# Preamp_protection.net
KiCad netlist of a schematic drawn in Altium Designer
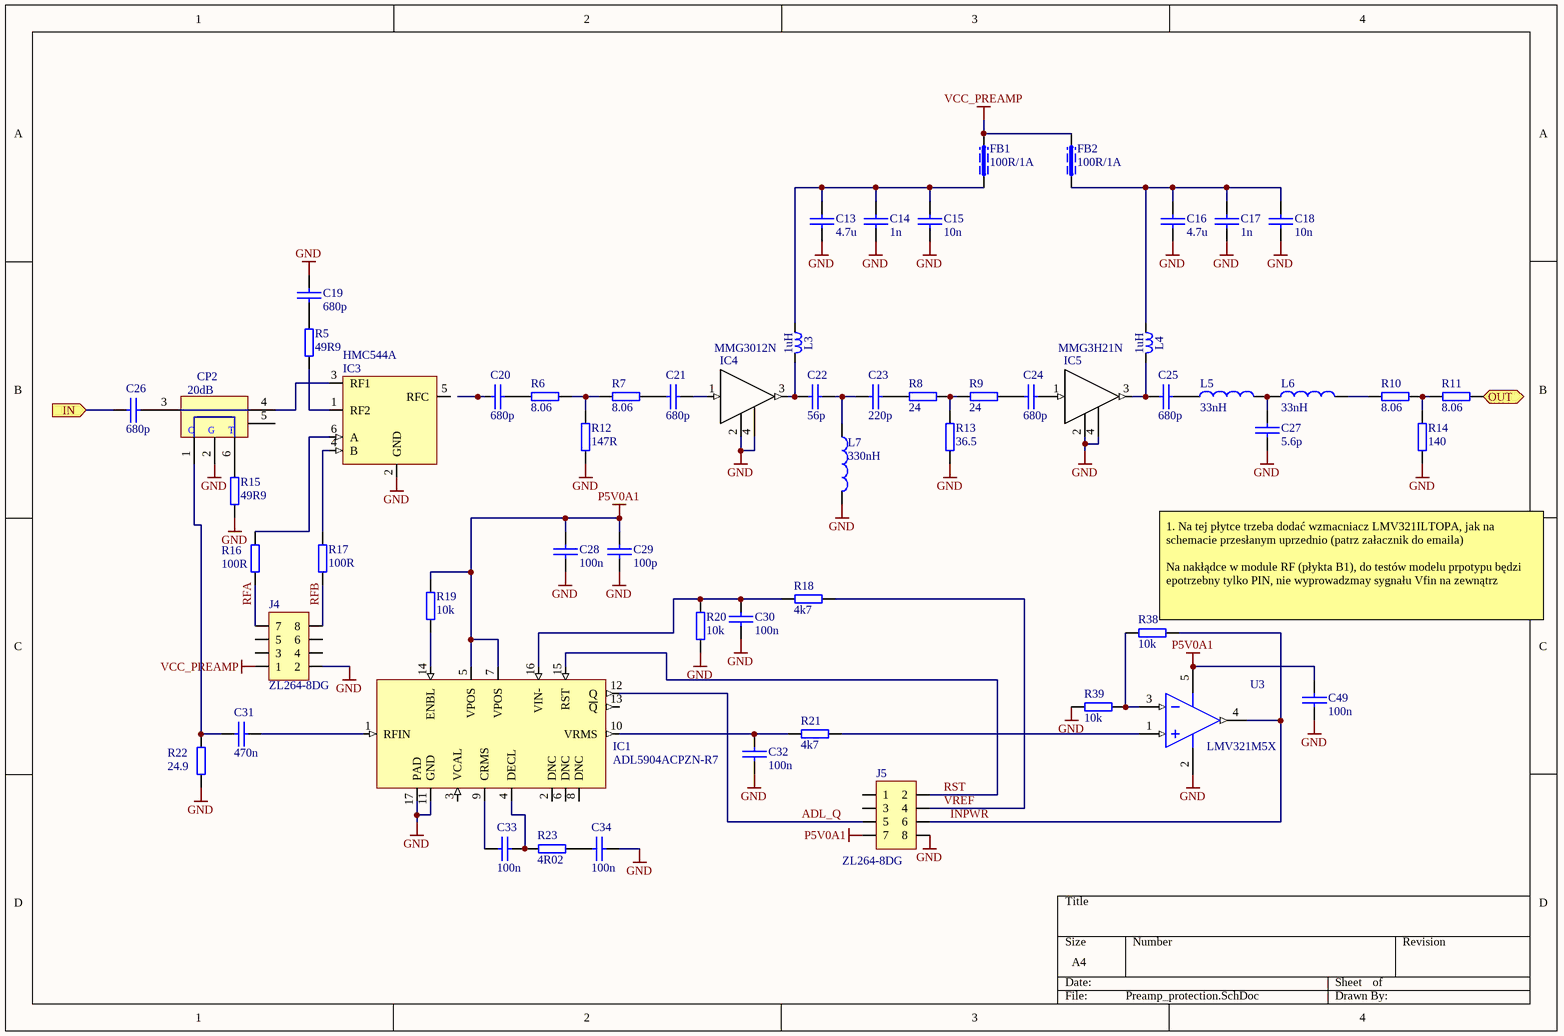
[diagram p0: Preamp_protection.SchDoc]

(export (version "E")
  (design (tool "Eeschema 10.0.6"))
  (components
    (comp (ref "C13")
      (value "4.7u")
      (footprint "0603C")
      (description "Capacitor SMD")
      (fields (field (name "PART") "GRM21BR71C475KE51L"))
      (libsource (lib "LIBRARY_SCH") (part "CAP_SMD_0603"))
    )
    (comp (ref "C14")
      (value "1n")
      (footprint "0603C")
      (description "Capacitor SMD")
      (fields (field (name "PART") "GRM1885C1H102JA01D"))
      (libsource (lib "LIBRARY_SCH") (part "CAP_SMD_0603"))
    )
    (comp (ref "C15")
      (value "10n")
      (footprint "0603C")
      (description "Capacitor SMD")
      (fields (field (name "PART") "GRM1885C1H103JA01D"))
      (libsource (lib "LIBRARY_SCH") (part "CAP_SMD_0603"))
    )
    (comp (ref "C16")
      (value "4.7u")
      (footprint "0603C")
      (description "Capacitor SMD")
      (fields (field (name "PART") "GRM21BR71C475KE51L"))
      (libsource (lib "LIBRARY_SCH") (part "CAP_SMD_0603"))
    )
    (comp (ref "C17")
      (value "1n")
      (footprint "0603C")
      (description "Capacitor SMD")
      (fields (field (name "PART") "GRM1885C1H102JA01D"))
      (libsource (lib "LIBRARY_SCH") (part "CAP_SMD_0603"))
    )
    (comp (ref "C18")
      (value "10n")
      (footprint "0603C")
      (description "Capacitor SMD")
      (fields (field (name "PART") "GRM1885C1H103JA01D"))
      (libsource (lib "LIBRARY_SCH") (part "CAP_SMD_0603"))
    )
    (comp (ref "C19")
      (value "680p")
      (footprint "0603C")
      (description "Capacitor SMD")
      (fields (field (name "PART") "GRM1555C1H681GA01"))
      (libsource (lib "LIBRARY_SCH") (part "CAP_SMD_0603"))
    )
    (comp (ref "C20")
      (value "680p")
      (footprint "0603C")
      (description "Capacitor SMD")
      (fields (field (name "PART") "GRM1555C1H681GA01"))
      (libsource (lib "LIBRARY_SCH") (part "CAP_SMD_0603"))
    )
    (comp (ref "C21")
      (value "680p")
      (footprint "0603C")
      (description "Capacitor SMD")
      (fields (field (name "PART") "GRM1555C1H681GA01"))
      (libsource (lib "LIBRARY_SCH") (part "CAP_SMD_0603"))
    )
    (comp (ref "C22")
      (value "56p")
      (footprint "0603C")
      (description "Capacitor SMD")
      (fields (field (name "PART") "GRM1885C1H560GA01J"))
      (libsource (lib "LIBRARY_SCH") (part "CAP_SMD_0603"))
    )
    (comp (ref "C23")
      (value "220p")
      (footprint "0603C")
      (description "Capacitor SMD")
      (fields (field (name "PART") "GRM1885C1H221GA01D"))
      (libsource (lib "LIBRARY_SCH") (part "CAP_SMD_0603"))
    )
    (comp (ref "C24")
      (value "680p")
      (footprint "0603C")
      (description "Capacitor SMD")
      (fields (field (name "PART") "GRM1555C1H681GA01"))
      (libsource (lib "LIBRARY_SCH") (part "CAP_SMD_0603"))
    )
    (comp (ref "C25")
      (value "680p")
      (footprint "0603C")
      (description "Capacitor SMD")
      (fields (field (name "PART") "GRM1555C1H681GA01"))
      (libsource (lib "LIBRARY_SCH") (part "CAP_SMD_0603"))
    )
    (comp (ref "C26")
      (value "680p")
      (footprint "0603C")
      (description "Capacitor SMD")
      (fields (field (name "PART") "GRM1555C1H681GA01"))
      (libsource (lib "LIBRARY_SCH") (part "CAP_SMD_0603"))
    )
    (comp (ref "C27")
      (value "5.6p")
      (footprint "0603C")
      (description "Capacitor SMD")
      (fields (field (name "PART") "GQM1885C2A5R6BB01D"))
      (libsource (lib "LIBRARY_SCH") (part "CAP_SMD_0603"))
    )
    (comp (ref "C28")
      (value "100n")
      (footprint "0603C")
      (description "Capacitor SMD")
      (fields (field (name "PART") "GRM188L81H104KA93D"))
      (libsource (lib "LIBRARY_SCH") (part "CAP_SMD_0603"))
    )
    (comp (ref "C29")
      (value "100p")
      (footprint "0603C")
      (description "Capacitor SMD")
      (fields (field (name "PART") "C1608NP01H101J080AA"))
      (libsource (lib "LIBRARY_SCH") (part "CAP_SMD_0603"))
    )
    (comp (ref "C30")
      (value "100n")
      (footprint "0603C")
      (description "Capacitor SMD")
      (fields (field (name "PART") "GRM188L81H104KA93D"))
      (libsource (lib "LIBRARY_SCH") (part "CAP_SMD_0603"))
    )
    (comp (ref "C31")
      (value "470n")
      (footprint "0603C")
      (description "Capacitor SMD")
      (fields (field (name "PART") "GRM188R71A474KA61D"))
      (libsource (lib "LIBRARY_SCH") (part "CAP_SMD_0603"))
    )
    (comp (ref "C32")
      (value "100n")
      (footprint "0603C")
      (description "Capacitor SMD")
      (fields (field (name "PART") "GRM188L81H104KA93D"))
      (libsource (lib "LIBRARY_SCH") (part "CAP_SMD_0603"))
    )
    (comp (ref "C33")
      (value "100n")
      (footprint "0603C")
      (description "Capacitor SMD")
      (fields (field (name "PART") "GRM188L81H104KA93D"))
      (libsource (lib "LIBRARY_SCH") (part "CAP_SMD_0603"))
    )
    (comp (ref "C34")
      (value "100n")
      (footprint "0603C")
      (description "Capacitor SMD")
      (fields (field (name "PART") "GRM188L81H104KA93D"))
      (libsource (lib "LIBRARY_SCH") (part "CAP_SMD_0603"))
    )
    (comp (ref "C49")
      (value "100n")
      (footprint "0603C")
      (description "Capacitor SMD")
      (fields (field (name "PART") "GRM188L81H104KA93D"))
      (libsource (lib "LIBRARY_SCH") (part "CAP_SMD_0603"))
    )
    (comp (ref "CP2")
      (value "20dB")
      (footprint "XFMR_MINI-CIRCUITS_AT224")
      (description "50 Ohms directional coupler")
      (fields
        (field (name "PART NUMBER") "XFMR_MINI-CIRCUITS_TCD-20-4X+")
        (field (name "MANUFACTURER") "MINI-CIRCUITS")
        (field (name "AUTHOR") "GK")
      )
      (libsource (lib "LIBRARY_SCH") (part "RF_Coupler_TCD-20-4X"))
    )
    (comp (ref "FB1")
      (value "100R/1A")
      (footprint "0603L")
      (description "ferrite bead 100R@100MHz 1A")
      (libsource (lib "LIBRARY_SCH") (part "L_FERRITE_BEAD_0603"))
    )
    (comp (ref "FB2")
      (value "100R/1A")
      (footprint "0603L")
      (description "ferrite bead 100R@100MHz 1A")
      (libsource (lib "LIBRARY_SCH") (part "L_FERRITE_BEAD_0603"))
    )
    (comp (ref "IC1")
      (value "ADL5904ACPZN-R7")
      (footprint "QFN50P300X300X80_HS-17N")
      (description "DC   to 6 GHz  , 45 dB DC  to 6 GHz , 45 dB TruPwr Detector with Envelope Threshold Detection")
      (libsource (lib "LIBRARY_SCH") (part "ADL5904"))
    )
    (comp (ref "IC3")
      (value "HMC544A")
      (footprint "SOT95P280X130-6N")
      (libsource (lib "LIBRARY_SCH") (part "RF_HMC544AE"))
    )
    (comp (ref "IC4")
      (value "MMG3012N")
      (footprint "SOT89-150P410X170-3N")
      (description "Broadband High Linearity Amplifier")
      (libsource (lib "LIBRARY_SCH") (part "RF_MMG3012N"))
    )
    (comp (ref "IC5")
      (value "MMG3H21N")
      (footprint "SOT89-150P410X170-3N")
      (description "Broadband High Linearity Amplifier")
      (libsource (lib "LIBRARY_SCH") (part "RF_MMG3H21N"))
    )
    (comp (ref "J4")
      (value "ZL264-8DG")
      (footprint "ZL264-8DG")
      (description "2.54mm pitch connector")
      (libsource (lib "") (part "CON_2X4 2.54 SMT FEM_1"))
    )
    (comp (ref "J5")
      (value "ZL264-8DG")
      (footprint "ZL264-8DG")
      (description "2.54mm pitch connector")
      (libsource (lib "LIBRARY_SCH") (part "CON_2X4 2.54 SMT FEM"))
    )
    (comp (ref "L3")
      (value "1uH")
      (footprint "INDP2520X18L")
      (description "100uH, 60mA, 21R")
      (fields (field (name "PART") "LQW2UAS1R0J00L") (field (name "AUTHOR") "GK"))
      (libsource (lib "LIBRARY_SCH") (part "L_1008_100u"))
    )
    (comp (ref "L4")
      (value "1uH")
      (footprint "INDP2520X18L")
      (description "100uH, 60mA, 21R")
      (fields (field (name "PART") "LQW2UAS1R0J00L") (field (name "AUTHOR") "GK"))
      (libsource (lib "LIBRARY_SCH") (part "L_1008_100u"))
    )
    (comp (ref "L5")
      (value "33nH")
      (footprint "0603L")
      (description "1uH, 25mA, 0.6R")
      (fields (field (name "PART") "LQW18AS33NG00D"))
      (libsource (lib "") (part "L_0603_1uH_1"))
    )
    (comp (ref "L6")
      (value "33nH")
      (footprint "0603L")
      (description "1uH, 25mA, 0.6R")
      (fields (field (name "PART") "LQW18AS33NG00D"))
      (libsource (lib "") (part "L_0603_1uH_1"))
    )
    (comp (ref "L7")
      (value "330nH")
      (footprint "0603L")
      (description "1uH, 25mA, 0.6R")
      (fields (field (name "PART") "LQW18ANR33G00D"))
      (libsource (lib "LIBRARY_SCH") (part "L_0603_1uH"))
    )
    (comp (ref "R5")
      (value "49R9")
      (footprint "0603R")
      (description "SMD Resistor")
      (fields (field (name "PART") "MCT0603PD4999DP500"))
      (libsource (lib "LIBRARY_SCH") (part "RES_0603"))
    )
    (comp (ref "R6")
      (value "8.06")
      (footprint "0603R")
      (description "SMD Resistor")
      (fields (field (name "PART") "CPF0805B8R06E1"))
      (libsource (lib "LIBRARY_SCH") (part "RES_0603"))
    )
    (comp (ref "R7")
      (value "8.06")
      (footprint "0603R")
      (description "SMD Resistor")
      (fields (field (name "PART") "CPF0805B8R06E1"))
      (libsource (lib "LIBRARY_SCH") (part "RES_0603"))
    )
    (comp (ref "R8")
      (value "24")
      (footprint "0603R")
      (description "SMD Resistor")
      (fields (field (name "PART") "CPF0805B24RE1"))
      (libsource (lib "LIBRARY_SCH") (part "RES_0603"))
    )
    (comp (ref "R9")
      (value "24")
      (footprint "0603R")
      (description "SMD Resistor")
      (fields (field (name "PART") "CPF0805B24RE1"))
      (libsource (lib "LIBRARY_SCH") (part "RES_0603"))
    )
    (comp (ref "R10")
      (value "8.06")
      (footprint "0603R")
      (description "SMD Resistor")
      (fields (field (name "PART") "CPF0805B8R06E1"))
      (libsource (lib "LIBRARY_SCH") (part "RES_0603"))
    )
    (comp (ref "R11")
      (value "8.06")
      (footprint "0603R")
      (description "SMD Resistor")
      (fields (field (name "PART") "CPF0805B8R06E1"))
      (libsource (lib "LIBRARY_SCH") (part "RES_0603"))
    )
    (comp (ref "R12")
      (value "147R")
      (footprint "0603R")
      (description "SMD Resistor")
      (fields (field (name "PART") "CPF0805B147RE1"))
      (libsource (lib "LIBRARY_SCH") (part "RES_0603"))
    )
    (comp (ref "R13")
      (value "36.5")
      (footprint "0603R")
      (description "SMD Resistor")
      (fields (field (name "PART") "CPF0805B36R5E1"))
      (libsource (lib "LIBRARY_SCH") (part "RES_0603"))
    )
    (comp (ref "R14")
      (value "140")
      (footprint "0603R")
      (description "SMD Resistor")
      (libsource (lib "LIBRARY_SCH") (part "RES_0603"))
    )
    (comp (ref "R15")
      (value "49R9")
      (footprint "0603R")
      (description "SMD Resistor")
      (fields (field (name "PART") "MCT0603PD4999DP500"))
      (libsource (lib "LIBRARY_SCH") (part "RES_0603"))
    )
    (comp (ref "R16")
      (value "100R")
      (footprint "0603R")
      (description "SMD Resistor")
      (fields (field (name "PART") "CRCW0603100RJNEA"))
      (libsource (lib "LIBRARY_SCH") (part "RES_0603"))
    )
    (comp (ref "R17")
      (value "100R")
      (footprint "0603R")
      (description "SMD Resistor")
      (fields (field (name "PART") "CRCW0603100RJNEA"))
      (libsource (lib "LIBRARY_SCH") (part "RES_0603"))
    )
    (comp (ref "R18")
      (value "4k7")
      (footprint "0603R")
      (description "SMD Resistor")
      (fields (field (name "PART") "CR0603-FX-4701ELF"))
      (libsource (lib "LIBRARY_SCH") (part "RES_0603"))
    )
    (comp (ref "R19")
      (value "10k")
      (footprint "0603R")
      (description "SMD Resistor")
      (fields (field (name "PART") "CRCW060310K0FKEA"))
      (libsource (lib "LIBRARY_SCH") (part "RES_0603"))
    )
    (comp (ref "R20")
      (value "10k")
      (footprint "0603R")
      (description "SMD Resistor")
      (fields (field (name "PART") "CRCW060310K0FKEA"))
      (libsource (lib "LIBRARY_SCH") (part "RES_0603"))
    )
    (comp (ref "R21")
      (value "4k7")
      (footprint "0603R")
      (description "SMD Resistor")
      (fields (field (name "PART") "CR0603-FX-4701ELF"))
      (libsource (lib "LIBRARY_SCH") (part "RES_0603"))
    )
    (comp (ref "R22")
      (value "24.9")
      (footprint "0603R")
      (description "SMD Resistor")
      (fields (field (name "PART") "CPF0603F24R9C1"))
      (libsource (lib "LIBRARY_SCH") (part "RES_0603"))
    )
    (comp (ref "R23")
      (value "4R02")
      (footprint "0603R")
      (description "SMD Resistor")
      (fields (field (name "PART") "CRCW06034R02FKEA"))
      (libsource (lib "LIBRARY_SCH") (part "RES_0603"))
    )
    (comp (ref "R38")
      (value "10k")
      (footprint "0603R")
      (description "SMD Resistor")
      (fields (field (name "PART") "CRCW060310K0FKEA"))
      (libsource (lib "LIBRARY_SCH") (part "RES_0603"))
    )
    (comp (ref "R39")
      (value "10k")
      (footprint "0603R")
      (description "SMD Resistor")
      (fields (field (name "PART") "CRCW060310K0FKEA"))
      (libsource (lib "LIBRARY_SCH") (part "RES_0603"))
    )
    (comp (ref "U3")
      (value "LMV321M5X")
      (footprint "DBV0005A_N")
      (description "General Purpose, Low Voltage, Rail-to-Rail Output Operational Amplifiers, 5-pin SOT-23")
      (fields (field (name "MANUFACTURER") "Texas Instruments"))
      (libsource (lib "Altium Content Vault") (part "AMP-OPA-LMV551-5"))
    )
  )
  (nets
    (net (code "1") (name "/ADL_Q") (class "Default")
      (node (ref "IC1") (pin "12") (pinfunction "Q_12") (pintype "output"))
      (node (ref "J5") (pin "5") (pinfunction "5_5") (pintype "passive"))
    )
    (net (code "2") (name "/IN") (class "Default")
      (node (ref "C26") (pin "1") (pinfunction "1_1") (pintype "passive"))
    )
    (net (code "3") (name "/INPWR") (class "Default")
      (node (ref "J5") (pin "6") (pinfunction "6_6") (pintype "passive"))
      (node (ref "R38") (pin "1") (pinfunction "1_1") (pintype "passive"))
      (node (ref "U3") (pin "4") (pinfunction "OUT_4") (pintype "output"))
    )
    (net (code "4") (name "/OUT") (class "Default")
      (node (ref "R11") (pin "1") (pinfunction "1_1") (pintype "passive"))
    )
    (net (code "5") (name "/RFA") (class "Default")
      (node (ref "J4") (pin "7") (pinfunction "7_7") (pintype "passive"))
      (node (ref "R16") (pin "2") (pinfunction "2_2") (pintype "passive"))
    )
    (net (code "6") (name "/RFB") (class "Default")
      (node (ref "J4") (pin "8") (pinfunction "8_8") (pintype "passive"))
      (node (ref "R17") (pin "2") (pinfunction "2_2") (pintype "passive"))
    )
    (net (code "7") (name "/RST") (class "Default")
      (node (ref "IC1") (pin "15") (pinfunction "RST_15") (pintype "input"))
      (node (ref "J5") (pin "2") (pinfunction "2_2") (pintype "passive"))
    )
    (net (code "8") (name "/VREF") (class "Default")
      (node (ref "J5") (pin "4") (pinfunction "4_4") (pintype "passive"))
      (node (ref "R18") (pin "1") (pinfunction "1_1") (pintype "passive"))
    )
    (net (code "9") (name "GND") (class "Default")
      (node (ref "C13") (pin "2") (pinfunction "2_2") (pintype "passive"))
      (node (ref "C14") (pin "2") (pinfunction "2_2") (pintype "passive"))
      (node (ref "C15") (pin "2") (pinfunction "2_2") (pintype "passive"))
      (node (ref "C16") (pin "2") (pinfunction "2_2") (pintype "passive"))
      (node (ref "C17") (pin "2") (pinfunction "2_2") (pintype "passive"))
      (node (ref "C18") (pin "2") (pinfunction "2_2") (pintype "passive"))
      (node (ref "C19") (pin "2") (pinfunction "2_2") (pintype "passive"))
      (node (ref "C27") (pin "1") (pinfunction "1_1") (pintype "passive"))
      (node (ref "C28") (pin "2") (pinfunction "2_2") (pintype "passive"))
      (node (ref "C29") (pin "2") (pinfunction "2_2") (pintype "passive"))
      (node (ref "C30") (pin "1") (pinfunction "1_1") (pintype "passive"))
      (node (ref "C32") (pin "1") (pinfunction "1_1") (pintype "passive"))
      (node (ref "C34") (pin "2") (pinfunction "2_2") (pintype "passive"))
      (node (ref "C49") (pin "1") (pinfunction "1_1") (pintype "passive"))
      (node (ref "CP2") (pin "2") (pinfunction "NC_2") (pintype "passive"))
      (node (ref "IC1") (pin "11") (pinfunction "GND_11") (pintype "power_in"))
      (node (ref "IC1") (pin "17") (pinfunction "PAD_17") (pintype "power_in"))
      (node (ref "IC3") (pin "2") (pinfunction "GND_2") (pintype "power_in"))
      (node (ref "IC4") (pin "2") (pinfunction "G_2") (pintype "power_in"))
      (node (ref "IC4") (pin "4") (pinfunction "G_4") (pintype "power_in"))
      (node (ref "IC5") (pin "2") (pinfunction "G_2") (pintype "power_in"))
      (node (ref "IC5") (pin "4") (pinfunction "G_4") (pintype "power_in"))
      (node (ref "J4") (pin "2") (pinfunction "2_2") (pintype "passive"))
      (node (ref "J5") (pin "8") (pinfunction "8_8") (pintype "passive"))
      (node (ref "L7") (pin "2") (pinfunction "2_2") (pintype "passive"))
      (node (ref "R12") (pin "1") (pinfunction "1_1") (pintype "passive"))
      (node (ref "R13") (pin "2") (pinfunction "2_2") (pintype "passive"))
      (node (ref "R14") (pin "2") (pinfunction "2_2") (pintype "passive"))
      (node (ref "R15") (pin "2") (pinfunction "2_2") (pintype "passive"))
      (node (ref "R20") (pin "1") (pinfunction "1_1") (pintype "passive"))
      (node (ref "R22") (pin "2") (pinfunction "2_2") (pintype "passive"))
      (node (ref "R39") (pin "2") (pinfunction "2_2") (pintype "passive"))
      (node (ref "U3") (pin "2") (pinfunction "V-_2") (pintype "power_in"))
    )
    (net (code "10") (name "Net-(C13-Pad1)") (class "Default")
      (node (ref "C13") (pin "1") (pinfunction "1_1") (pintype "passive"))
      (node (ref "C14") (pin "1") (pinfunction "1_1") (pintype "passive"))
      (node (ref "C15") (pin "1") (pinfunction "1_1") (pintype "passive"))
      (node (ref "FB1") (pin "1") (pinfunction "1_1") (pintype "passive"))
      (node (ref "L3") (pin "1") (pinfunction "1_1") (pintype "passive"))
    )
    (net (code "11") (name "Net-(C16-Pad1)") (class "Default")
      (node (ref "C16") (pin "1") (pinfunction "1_1") (pintype "passive"))
      (node (ref "C17") (pin "1") (pinfunction "1_1") (pintype "passive"))
      (node (ref "C18") (pin "1") (pinfunction "1_1") (pintype "passive"))
      (node (ref "FB2") (pin "1") (pinfunction "1_1") (pintype "passive"))
      (node (ref "L4") (pin "1") (pinfunction "1_1") (pintype "passive"))
    )
    (net (code "12") (name "Net-(C19-Pad1)") (class "Default")
      (node (ref "C19") (pin "1") (pinfunction "1_1") (pintype "passive"))
      (node (ref "R5") (pin "1") (pinfunction "1_1") (pintype "passive"))
    )
    (net (code "13") (name "Net-(C20-Pad2)") (class "Default")
      (node (ref "C20") (pin "2") (pinfunction "2_2") (pintype "passive"))
      (node (ref "R6") (pin "2") (pinfunction "2_2") (pintype "passive"))
    )
    (net (code "14") (name "Net-(C21-Pad1)") (class "Default")
      (node (ref "C21") (pin "1") (pinfunction "1_1") (pintype "passive"))
      (node (ref "R7") (pin "1") (pinfunction "1_1") (pintype "passive"))
    )
    (net (code "15") (name "Net-(C22-Pad2)") (class "Default")
      (node (ref "C22") (pin "2") (pinfunction "2_2") (pintype "passive"))
      (node (ref "C23") (pin "1") (pinfunction "1_1") (pintype "passive"))
      (node (ref "L7") (pin "1") (pinfunction "1_1") (pintype "passive"))
    )
    (net (code "16") (name "Net-(C23-Pad2)") (class "Default")
      (node (ref "C23") (pin "2") (pinfunction "2_2") (pintype "passive"))
      (node (ref "R8") (pin "2") (pinfunction "2_2") (pintype "passive"))
    )
    (net (code "17") (name "Net-(C24-Pad1)") (class "Default")
      (node (ref "C24") (pin "1") (pinfunction "1_1") (pintype "passive"))
      (node (ref "R9") (pin "1") (pinfunction "1_1") (pintype "passive"))
    )
    (net (code "18") (name "Net-(C25-Pad2)") (class "Default")
      (node (ref "C25") (pin "2") (pinfunction "2_2") (pintype "passive"))
      (node (ref "L5") (pin "1") (pinfunction "1_1") (pintype "passive"))
    )
    (net (code "19") (name "Net-(C27-Pad2)") (class "Default")
      (node (ref "C27") (pin "2") (pinfunction "2_2") (pintype "passive"))
      (node (ref "L5") (pin "2") (pinfunction "2_2") (pintype "passive"))
      (node (ref "L6") (pin "1") (pinfunction "1_1") (pintype "passive"))
    )
    (net (code "20") (name "Net-(C34-Pad1)") (class "Default")
      (node (ref "C34") (pin "1") (pinfunction "1_1") (pintype "passive"))
      (node (ref "R23") (pin "2") (pinfunction "2_2") (pintype "passive"))
    )
    (net (code "21") (name "Net-(CP2-PDOT)") (class "Default")
      (node (ref "CP2") (pin "6") (pinfunction "PDOT_6") (pintype "passive"))
      (node (ref "R15") (pin "1") (pinfunction "1_1") (pintype "passive"))
    )
    (net (code "22") (name "Net-(CP2-S)") (class "Default")
      (node (ref "C26") (pin "2") (pinfunction "2_2") (pintype "passive"))
      (node (ref "CP2") (pin "3") (pinfunction "S_3") (pintype "passive"))
    )
    (net (code "23") (name "Net-(CP2-SDOT)") (class "Default")
      (node (ref "C31") (pin "1") (pinfunction "1_1") (pintype "passive"))
      (node (ref "CP2") (pin "1") (pinfunction "SDOT_1") (pintype "passive"))
      (node (ref "R22") (pin "1") (pinfunction "1_1") (pintype "passive"))
    )
    (net (code "24") (name "Net-(IC1-CRMS)") (class "Default")
      (node (ref "C33") (pin "1") (pinfunction "1_1") (pintype "passive"))
      (node (ref "IC1") (pin "9") (pinfunction "CRMS_9") (pintype "passive"))
    )
    (net (code "25") (name "Net-(IC1-DECL)") (class "Default")
      (node (ref "C33") (pin "2") (pinfunction "2_2") (pintype "passive"))
      (node (ref "IC1") (pin "4") (pinfunction "DECL_4") (pintype "passive"))
      (node (ref "R23") (pin "1") (pinfunction "1_1") (pintype "passive"))
    )
    (net (code "26") (name "Net-(IC1-ENBL)") (class "Default")
      (node (ref "IC1") (pin "14") (pinfunction "ENBL_14") (pintype "input"))
      (node (ref "R19") (pin "2") (pinfunction "2_2") (pintype "passive"))
    )
    (net (code "27") (name "Net-(IC1-RFIN)") (class "Default")
      (node (ref "C31") (pin "2") (pinfunction "2_2") (pintype "passive"))
      (node (ref "IC1") (pin "1") (pinfunction "RFIN_1") (pintype "input"))
    )
    (net (code "28") (name "Net-(IC1-VIN-)") (class "Default")
      (node (ref "C30") (pin "2") (pinfunction "2_2") (pintype "passive"))
      (node (ref "IC1") (pin "16") (pinfunction "VIN-_16") (pintype "input"))
      (node (ref "R18") (pin "2") (pinfunction "2_2") (pintype "passive"))
      (node (ref "R20") (pin "2") (pinfunction "2_2") (pintype "passive"))
    )
    (net (code "29") (name "Net-(IC1-VRMS)") (class "Default")
      (node (ref "C32") (pin "2") (pinfunction "2_2") (pintype "passive"))
      (node (ref "IC1") (pin "10") (pinfunction "VRMS_10") (pintype "output"))
      (node (ref "R21") (pin "2") (pinfunction "2_2") (pintype "passive"))
    )
    (net (code "30") (name "Net-(IC3-A)") (class "Default")
      (node (ref "IC3") (pin "6") (pinfunction "A_6") (pintype "input"))
      (node (ref "R16") (pin "1") (pinfunction "1_1") (pintype "passive"))
    )
    (net (code "31") (name "Net-(IC3-B)") (class "Default")
      (node (ref "IC3") (pin "4") (pinfunction "B_4") (pintype "input"))
      (node (ref "R17") (pin "1") (pinfunction "1_1") (pintype "passive"))
    )
    (net (code "32") (name "Net-(IC3-RF1)") (class "Default")
      (node (ref "CP2") (pin "4") (pinfunction "P_4") (pintype "passive"))
      (node (ref "IC3") (pin "3") (pinfunction "RF1_3") (pintype "bidirectional"))
    )
    (net (code "33") (name "Net-(IC3-RF2)") (class "Default")
      (node (ref "IC3") (pin "1") (pinfunction "RF2_1") (pintype "bidirectional"))
      (node (ref "R5") (pin "2") (pinfunction "2_2") (pintype "passive"))
    )
    (net (code "34") (name "Net-(IC4-IN)") (class "Default")
      (node (ref "C21") (pin "2") (pinfunction "2_2") (pintype "passive"))
      (node (ref "IC4") (pin "1") (pinfunction "IN_1") (pintype "input"))
    )
    (net (code "35") (name "Net-(IC4-OUT)") (class "Default")
      (node (ref "C22") (pin "1") (pinfunction "1_1") (pintype "passive"))
      (node (ref "IC4") (pin "3") (pinfunction "OUT_3") (pintype "output"))
      (node (ref "L3") (pin "2") (pinfunction "2_2") (pintype "passive"))
    )
    (net (code "36") (name "Net-(IC5-IN)") (class "Default")
      (node (ref "C24") (pin "2") (pinfunction "2_2") (pintype "passive"))
      (node (ref "IC5") (pin "1") (pinfunction "IN_1") (pintype "input"))
    )
    (net (code "37") (name "Net-(IC5-OUT)") (class "Default")
      (node (ref "C25") (pin "1") (pinfunction "1_1") (pintype "passive"))
      (node (ref "IC5") (pin "3") (pinfunction "OUT_3") (pintype "output"))
      (node (ref "L4") (pin "2") (pinfunction "2_2") (pintype "passive"))
    )
    (net (code "38") (name "Net-(L6-Pad2)") (class "Default")
      (node (ref "L6") (pin "2") (pinfunction "2_2") (pintype "passive"))
      (node (ref "R10") (pin "2") (pinfunction "2_2") (pintype "passive"))
    )
    (net (code "39") (name "Net-(R10-Pad1)") (class "Default")
      (node (ref "R10") (pin "1") (pinfunction "1_1") (pintype "passive"))
      (node (ref "R11") (pin "2") (pinfunction "2_2") (pintype "passive"))
      (node (ref "R14") (pin "1") (pinfunction "1_1") (pintype "passive"))
    )
    (net (code "40") (name "Net-(R12-Pad2)") (class "Default")
      (node (ref "R12") (pin "2") (pinfunction "2_2") (pintype "passive"))
      (node (ref "R6") (pin "1") (pinfunction "1_1") (pintype "passive"))
      (node (ref "R7") (pin "2") (pinfunction "2_2") (pintype "passive"))
    )
    (net (code "41") (name "Net-(R13-Pad1)") (class "Default")
      (node (ref "R13") (pin "1") (pinfunction "1_1") (pintype "passive"))
      (node (ref "R8") (pin "1") (pinfunction "1_1") (pintype "passive"))
      (node (ref "R9") (pin "2") (pinfunction "2_2") (pintype "passive"))
    )
    (net (code "42") (name "Net-(U3-IN+)") (class "Default")
      (node (ref "R21") (pin "1") (pinfunction "1_1") (pintype "passive"))
      (node (ref "U3") (pin "1") (pinfunction "IN+_1") (pintype "input"))
    )
    (net (code "43") (name "Net-(U3-IN-)") (class "Default")
      (node (ref "R38") (pin "2") (pinfunction "2_2") (pintype "passive"))
      (node (ref "R39") (pin "1") (pinfunction "1_1") (pintype "passive"))
      (node (ref "U3") (pin "3") (pinfunction "IN-_3") (pintype "input"))
    )
    (net (code "44") (name "P5V0A1") (class "Default")
      (node (ref "C28") (pin "1") (pinfunction "1_1") (pintype "passive"))
      (node (ref "C29") (pin "1") (pinfunction "1_1") (pintype "passive"))
      (node (ref "C49") (pin "2") (pinfunction "2_2") (pintype "passive"))
      (node (ref "IC1") (pin "5") (pinfunction "VPOS_5") (pintype "power_in"))
      (node (ref "IC1") (pin "7") (pinfunction "VPOS_7") (pintype "power_in"))
      (node (ref "J5") (pin "7") (pinfunction "7_7") (pintype "passive"))
      (node (ref "R19") (pin "1") (pinfunction "1_1") (pintype "passive"))
      (node (ref "U3") (pin "5") (pinfunction "V+_5") (pintype "power_in"))
    )
    (net (code "45") (name "VCC_PREAMP") (class "Default")
      (node (ref "FB1") (pin "2") (pinfunction "2_2") (pintype "passive"))
      (node (ref "FB2") (pin "2") (pinfunction "2_2") (pintype "passive"))
      (node (ref "J4") (pin "1") (pinfunction "1_1") (pintype "passive"))
    )
    (net (code "46") (name "unconnected-(C20-Pad1)") (class "Default")
      (node (ref "C20") (pin "1") (pinfunction "1_1") (pintype "passive"))
    )
    (net (code "47") (name "unconnected-(CP2-P-Pad5)") (class "Default")
      (node (ref "CP2") (pin "5") (pinfunction "P_5") (pintype "passive"))
    )
    (net (code "48") (name "unconnected-(IC1-DNC-Pad2)") (class "Default")
      (node (ref "IC1") (pin "2") (pinfunction "DNC_2") (pintype "passive"))
    )
    (net (code "49") (name "unconnected-(IC1-DNC-Pad6)") (class "Default")
      (node (ref "IC1") (pin "6") (pinfunction "DNC_6") (pintype "passive"))
    )
    (net (code "50") (name "unconnected-(IC1-DNC-Pad8)") (class "Default")
      (node (ref "IC1") (pin "8") (pinfunction "DNC_8") (pintype "passive"))
    )
    (net (code "51") (name "unconnected-(IC1-VCAL-Pad3)") (class "Default")
      (node (ref "IC1") (pin "3") (pinfunction "VCAL_3") (pintype "input"))
    )
    (net (code "52") (name "unconnected-(IC1-~{Q}-Pad13)") (class "Default")
      (node (ref "IC1") (pin "13") (pinfunction "~{Q}_13") (pintype "output"))
    )
    (net (code "53") (name "unconnected-(IC3-RFC-Pad5)") (class "Default")
      (node (ref "IC3") (pin "5") (pinfunction "RFC_5") (pintype "bidirectional"))
    )
    (net (code "54") (name "unconnected-(J4-Pad3)") (class "Default")
      (node (ref "J4") (pin "3") (pinfunction "3_3") (pintype "passive"))
    )
    (net (code "55") (name "unconnected-(J4-Pad4)") (class "Default")
      (node (ref "J4") (pin "4") (pinfunction "4_4") (pintype "passive"))
    )
    (net (code "56") (name "unconnected-(J4-Pad5)") (class "Default")
      (node (ref "J4") (pin "5") (pinfunction "5_5") (pintype "passive"))
    )
    (net (code "57") (name "unconnected-(J4-Pad6)") (class "Default")
      (node (ref "J4") (pin "6") (pinfunction "6_6") (pintype "passive"))
    )
    (net (code "58") (name "unconnected-(J5-Pad1)") (class "Default")
      (node (ref "J5") (pin "1") (pinfunction "1_1") (pintype "passive"))
    )
    (net (code "59") (name "unconnected-(J5-Pad3)") (class "Default")
      (node (ref "J5") (pin "3") (pinfunction "3_3") (pintype "passive"))
    )
  )
)
